# t44_PWM.net
KiCad netlist of a schematic drawn in EAGLE
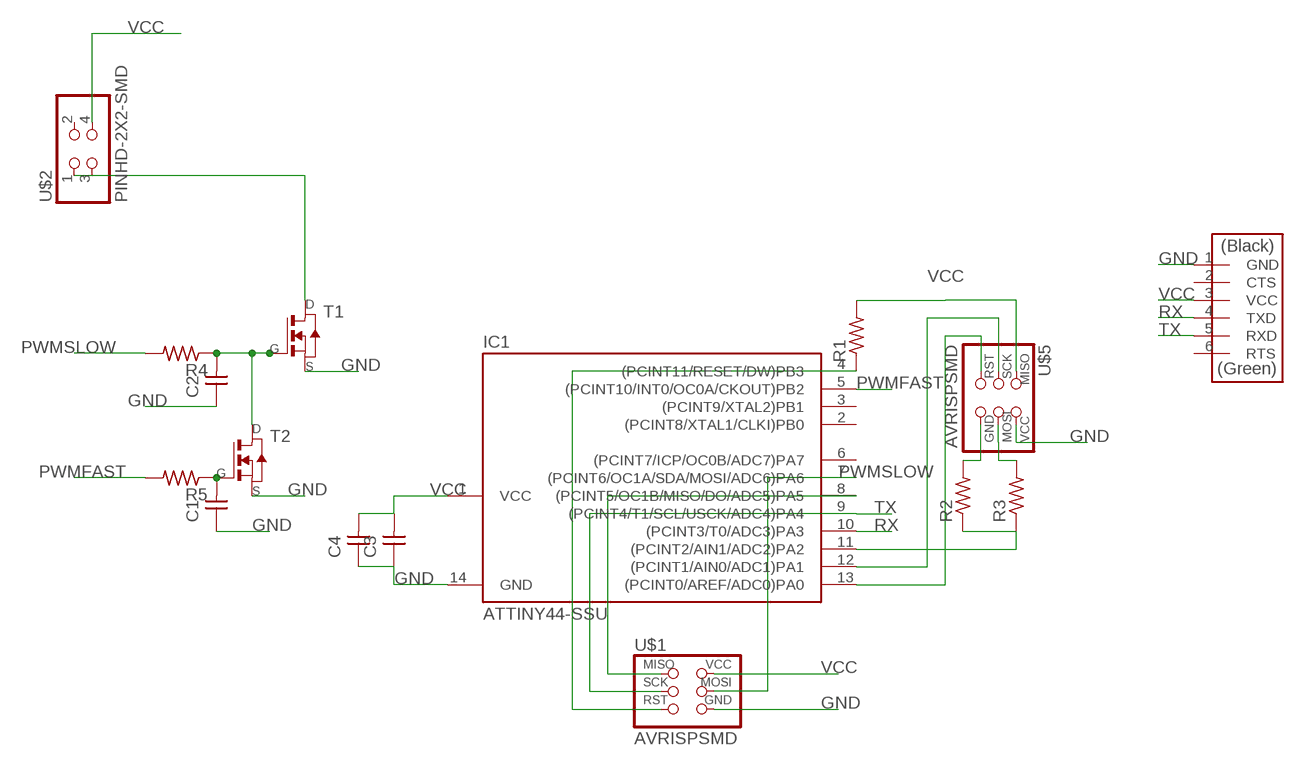
[diagram p0: schematic, sheet 1]

(export (version "E")
  (design (tool "Eeschema 10.0.6"))
  (components
    (comp (ref "C1")
      (value "CAP-UNPOLARIZED")
      (footprint "eagle-import:C1206")
      (libsource (lib "eagle-import") (part "CAP-UNPOLARIZED"))
    )
    (comp (ref "C2")
      (value "CAP-UNPOLARIZED")
      (footprint "eagle-import:C1206")
      (libsource (lib "eagle-import") (part "CAP-UNPOLARIZED"))
    )
    (comp (ref "C3")
      (value "CAP-UNPOLARIZED")
      (footprint "eagle-import:C1206")
      (libsource (lib "eagle-import") (part "CAP-UNPOLARIZED"))
    )
    (comp (ref "C4")
      (value "CAP-UNPOLARIZED")
      (footprint "eagle-import:C1206")
      (libsource (lib "eagle-import") (part "CAP-UNPOLARIZED"))
    )
    (comp (ref "IC1")
      (value "ATTINY44-SSU")
      (footprint "eagle-import:SOIC14")
      (libsource (lib "eagle-import") (part "ATTINY44-SSU"))
    )
    (comp (ref "R1")
      (value "RES-US1206")
      (footprint "eagle-import:R1206")
      (libsource (lib "eagle-import") (part "RES-US1206"))
    )
    (comp (ref "R2")
      (value "RES-US1206")
      (footprint "eagle-import:R1206")
      (libsource (lib "eagle-import") (part "RES-US1206"))
    )
    (comp (ref "R3")
      (value "RES-US1206")
      (footprint "eagle-import:R1206")
      (libsource (lib "eagle-import") (part "RES-US1206"))
    )
    (comp (ref "R4")
      (value "RES-US1206")
      (footprint "eagle-import:R1206")
      (libsource (lib "eagle-import") (part "RES-US1206"))
    )
    (comp (ref "R5")
      (value "RES-US1206")
      (footprint "eagle-import:R1206")
      (libsource (lib "eagle-import") (part "RES-US1206"))
    )
    (comp (ref "T1")
      (value "NMOSFETSOT23")
      (footprint "eagle-import:SOT-23")
      (libsource (lib "eagle-import") (part "NMOSFETSOT23"))
    )
    (comp (ref "T2")
      (value "NMOSFETSOT23")
      (footprint "eagle-import:SOT-23")
      (libsource (lib "eagle-import") (part "NMOSFETSOT23"))
    )
    (comp (ref "U$1")
      (value "AVRISPSMD")
      (footprint "eagle-import:2X03SMD")
      (libsource (lib "eagle-import") (part "fabcopy_AVRISPSMD"))
    )
    (comp (ref "U$2")
      (value "PINHD-2X2-SMD")
      (footprint "eagle-import:2X02SMD")
      (libsource (lib "eagle-import") (part "PINHD-2X2-SMD"))
    )
    (comp (ref "U$4")
      (value "FTDI-SMD-HEADER")
      (footprint "eagle-import:1X06SMD")
      (libsource (lib "eagle-import") (part "FTDI-SMD-HEADER"))
    )
    (comp (ref "U$5")
      (value "AVRISPSMD")
      (footprint "eagle-import:2X03SMD")
      (libsource (lib "eagle-import") (part "AVRISPSMD"))
    )
  )
  (nets
    (net (code "1") (name "/GND") (class "Default")
      (node (ref "C1") (pin "1") (pinfunction "1_1") (pintype "passive"))
      (node (ref "C2") (pin "1") (pinfunction "1_1") (pintype "passive"))
      (node (ref "C3") (pin "1") (pinfunction "1_1") (pintype "passive"))
      (node (ref "C4") (pin "1") (pinfunction "1_1") (pintype "passive"))
      (node (ref "IC1") (pin "14") (pinfunction "GND_14") (pintype "power_in"))
      (node (ref "T1") (pin "2") (pinfunction "S_2") (pintype "passive"))
      (node (ref "T2") (pin "2") (pinfunction "S_2") (pintype "passive"))
      (node (ref "U$1") (pin "6") (pinfunction "GND_6") (pintype "passive"))
      (node (ref "U$4") (pin "1") (pinfunction "GND_1") (pintype "bidirectional"))
      (node (ref "U$5") (pin "2") (pinfunction "VCC_2") (pintype "passive"))
    )
    (net (code "2") (name "/PWMFAST") (class "Default")
      (node (ref "IC1") (pin "5") (pinfunction "(PCINT10/INT0/OC0A/CKOUT)PB2_5") (pintype "bidirectional"))
      (node (ref "R5") (pin "2") (pinfunction "2_2") (pintype "passive"))
    )
    (net (code "3") (name "/PWMSLOW") (class "Default")
      (node (ref "IC1") (pin "7") (pinfunction "(PCINT6/OC1A/SDA/MOSI/ADC6)PA6_7") (pintype "bidirectional"))
      (node (ref "R4") (pin "2") (pinfunction "2_2") (pintype "passive"))
      (node (ref "U$1") (pin "4") (pinfunction "MOSI_4") (pintype "passive"))
    )
    (net (code "4") (name "/RX") (class "Default")
      (node (ref "IC1") (pin "10") (pinfunction "(PCINT3/T0/ADC3)PA3_10") (pintype "bidirectional"))
      (node (ref "U$4") (pin "4") (pinfunction "TXD_4") (pintype "bidirectional"))
    )
    (net (code "5") (name "/TX") (class "Default")
      (node (ref "IC1") (pin "9") (pinfunction "(PCINT4/T1/SCL/USCK/ADC4)PA4_9") (pintype "bidirectional"))
      (node (ref "U$1") (pin "3") (pinfunction "SCK_3") (pintype "passive"))
      (node (ref "U$4") (pin "5") (pinfunction "RXD_5") (pintype "bidirectional"))
    )
    (net (code "6") (name "/VCC") (class "Default")
      (node (ref "C3") (pin "2") (pinfunction "2_2") (pintype "passive"))
      (node (ref "C4") (pin "2") (pinfunction "2_2") (pintype "passive"))
      (node (ref "IC1") (pin "1") (pinfunction "VCC_1") (pintype "power_in"))
      (node (ref "R1") (pin "2") (pinfunction "2_2") (pintype "passive"))
      (node (ref "U$1") (pin "2") (pinfunction "VCC_2") (pintype "passive"))
      (node (ref "U$2") (pin "4") (pinfunction "4_4") (pintype "passive"))
      (node (ref "U$4") (pin "3") (pinfunction "VCC_3") (pintype "bidirectional"))
      (node (ref "U$5") (pin "1") (pinfunction "MISO_1") (pintype "passive"))
    )
    (net (code "7") (name "Net-(IC1-(PCINT0{slash}AREF{slash}ADC0)PA0)") (class "Default")
      (node (ref "IC1") (pin "13") (pinfunction "(PCINT0/AREF/ADC0)PA0_13") (pintype "bidirectional"))
      (node (ref "U$5") (pin "5") (pinfunction "RST_5") (pintype "passive"))
    )
    (net (code "8") (name "Net-(IC1-(PCINT1{slash}AIN0{slash}ADC1)PA1)") (class "Default")
      (node (ref "IC1") (pin "12") (pinfunction "(PCINT1/AIN0/ADC1)PA1_12") (pintype "bidirectional"))
      (node (ref "U$5") (pin "3") (pinfunction "SCK_3") (pintype "passive"))
    )
    (net (code "9") (name "Net-(IC1-(PCINT2{slash}AIN1{slash}ADC2)PA2)") (class "Default")
      (node (ref "IC1") (pin "11") (pinfunction "(PCINT2/AIN1/ADC2)PA2_11") (pintype "bidirectional"))
      (node (ref "R2") (pin "1") (pinfunction "1_1") (pintype "passive"))
      (node (ref "R3") (pin "1") (pinfunction "1_1") (pintype "passive"))
    )
    (net (code "10") (name "Net-(IC1-(PCINT5{slash}OC1B{slash}MISO{slash}DO{slash}ADC5)PA5)") (class "Default")
      (node (ref "IC1") (pin "8") (pinfunction "(PCINT5/OC1B/MISO/DO/ADC5)PA5_8") (pintype "bidirectional"))
      (node (ref "U$1") (pin "1") (pinfunction "MISO_1") (pintype "passive"))
    )
    (net (code "11") (name "Net-(IC1-(PCINT11{slash}RESET{slash}DW)PB3)") (class "Default")
      (node (ref "IC1") (pin "4") (pinfunction "(PCINT11/RESET/DW)PB3_4") (pintype "bidirectional"))
      (node (ref "R1") (pin "1") (pinfunction "1_1") (pintype "passive"))
      (node (ref "U$1") (pin "5") (pinfunction "RST_5") (pintype "passive"))
    )
    (net (code "12") (name "Net-(T1-D)") (class "Default")
      (node (ref "T1") (pin "1") (pinfunction "D_1") (pintype "passive"))
      (node (ref "U$2") (pin "1") (pinfunction "1_1") (pintype "passive"))
      (node (ref "U$2") (pin "3") (pinfunction "3_3") (pintype "passive"))
    )
    (net (code "13") (name "Net-(T1-G)") (class "Default")
      (node (ref "C2") (pin "2") (pinfunction "2_2") (pintype "passive"))
      (node (ref "R4") (pin "1") (pinfunction "1_1") (pintype "passive"))
      (node (ref "T1") (pin "3") (pinfunction "G_3") (pintype "passive"))
      (node (ref "T2") (pin "1") (pinfunction "D_1") (pintype "passive"))
    )
    (net (code "14") (name "Net-(T2-G)") (class "Default")
      (node (ref "C1") (pin "2") (pinfunction "2_2") (pintype "passive"))
      (node (ref "R5") (pin "1") (pinfunction "1_1") (pintype "passive"))
      (node (ref "T2") (pin "3") (pinfunction "G_3") (pintype "passive"))
    )
    (net (code "15") (name "Net-(U$5-GND)") (class "Default")
      (node (ref "R2") (pin "2") (pinfunction "2_2") (pintype "passive"))
      (node (ref "U$5") (pin "6") (pinfunction "GND_6") (pintype "passive"))
    )
    (net (code "16") (name "Net-(U$5-MOSI)") (class "Default")
      (node (ref "R3") (pin "2") (pinfunction "2_2") (pintype "passive"))
      (node (ref "U$5") (pin "4") (pinfunction "MOSI_4") (pintype "passive"))
    )
    (net (code "17") (name "unconnected-(IC1-(PCINT7{slash}ICP{slash}OC0B{slash}ADC7)PA7-Pad6)") (class "Default")
      (node (ref "IC1") (pin "6") (pinfunction "(PCINT7/ICP/OC0B/ADC7)PA7_6") (pintype "bidirectional"))
    )
    (net (code "18") (name "unconnected-(IC1-(PCINT8{slash}XTAL1{slash}CLKI)PB0-Pad2)") (class "Default")
      (node (ref "IC1") (pin "2") (pinfunction "(PCINT8/XTAL1/CLKI)PB0_2") (pintype "bidirectional"))
    )
    (net (code "19") (name "unconnected-(IC1-(PCINT9{slash}XTAL2)PB1-Pad3)") (class "Default")
      (node (ref "IC1") (pin "3") (pinfunction "(PCINT9/XTAL2)PB1_3") (pintype "bidirectional"))
    )
    (net (code "20") (name "unconnected-(U$2-Pad2)") (class "Default")
      (node (ref "U$2") (pin "2") (pinfunction "2_2") (pintype "passive"))
    )
    (net (code "21") (name "unconnected-(U$4-CTS-Pad2)") (class "Default")
      (node (ref "U$4") (pin "2") (pinfunction "CTS_2") (pintype "bidirectional"))
    )
    (net (code "22") (name "unconnected-(U$4-RTS-Pad6)") (class "Default")
      (node (ref "U$4") (pin "6") (pinfunction "RTS_6") (pintype "bidirectional"))
    )
  )
)
